# g29_load_cell.net
KiCad netlist of a schematic drawn in EAGLE
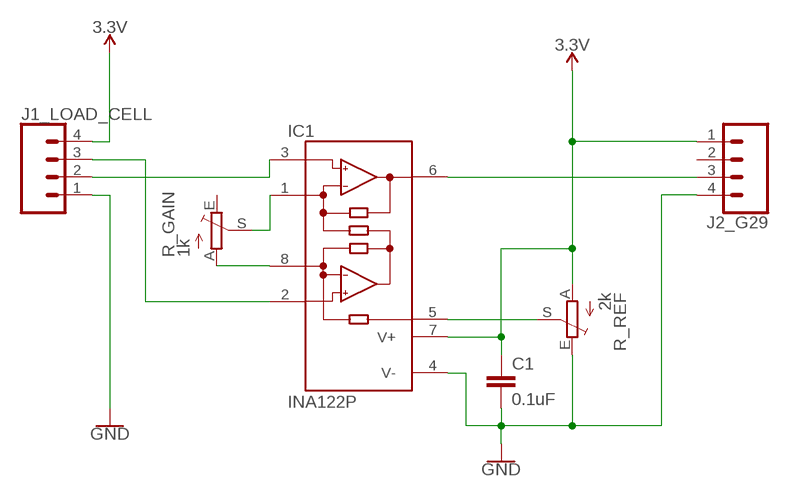
[diagram p0: schematic, sheet 1]

(export (version "E")
  (design (tool "Eeschema 10.0.6"))
  (components
    (comp (ref "C1")
      (value "0.1uF")
      (footprint "eagle-import:C025-024X044")
      (libsource (lib "eagle-import") (part "C-EU025-024X044"))
    )
    (comp (ref "IC1")
      (value "INA122P")
      (footprint "eagle-import:DIL08")
      (fields (field (name "MF") "TEXAS INSTRUMENTS"))
      (libsource (lib "eagle-import") (part "INA122P"))
    )
    (comp (ref "J1_LOAD_CELL")
      (value "CONN_04SCREW")
      (footprint "eagle-import:SCREWTERMINAL-3.5MM-4")
      (libsource (lib "eagle-import") (part "CONN_04SCREW"))
    )
    (comp (ref "J2_G29")
      (value "CONN_04SCREW")
      (footprint "eagle-import:SCREWTERMINAL-3.5MM-4")
      (libsource (lib "eagle-import") (part "CONN_04SCREW"))
    )
    (comp (ref "R_GAIN")
      (value "1k")
      (footprint "eagle-import:RJ9W")
      (libsource (lib "eagle-import") (part "TRIM_EU-RJ9W"))
    )
    (comp (ref "R_REF")
      (value "2k")
      (footprint "eagle-import:RJ9W")
      (libsource (lib "eagle-import") (part "TRIM_EU-RJ9W"))
    )
  )
  (nets
    (net (code "1") (name "3.3V") (class "Default")
      (node (ref "C1") (pin "1") (pinfunction "1_1") (pintype "passive"))
      (node (ref "IC1") (pin "7") (pinfunction "V+_7") (pintype "power_in"))
      (node (ref "J1_LOAD_CELL") (pin "4") (pinfunction "4_4") (pintype "passive"))
      (node (ref "J2_G29") (pin "1") (pinfunction "1_1") (pintype "passive"))
      (node (ref "R_REF") (pin "A") (pinfunction "A_A") (pintype "passive"))
    )
    (net (code "2") (name "GND") (class "Default")
      (node (ref "C1") (pin "2") (pinfunction "2_2") (pintype "passive"))
      (node (ref "IC1") (pin "4") (pinfunction "V-_4") (pintype "power_in"))
      (node (ref "J1_LOAD_CELL") (pin "1") (pinfunction "1_1") (pintype "passive"))
      (node (ref "J2_G29") (pin "4") (pinfunction "4_4") (pintype "passive"))
      (node (ref "R_REF") (pin "E") (pinfunction "E_E") (pintype "passive"))
    )
    (net (code "3") (name "Net-(IC1-+IN)") (class "Default")
      (node (ref "IC1") (pin "3") (pinfunction "+IN_3") (pintype "input"))
      (node (ref "J1_LOAD_CELL") (pin "2") (pinfunction "2_2") (pintype "passive"))
    )
    (net (code "4") (name "Net-(IC1--IN)") (class "Default")
      (node (ref "IC1") (pin "2") (pinfunction "-IN_2") (pintype "input"))
      (node (ref "J1_LOAD_CELL") (pin "3") (pinfunction "3_3") (pintype "passive"))
    )
    (net (code "5") (name "Net-(IC1-OUT)") (class "Default")
      (node (ref "IC1") (pin "6") (pinfunction "OUT_6") (pintype "output"))
      (node (ref "J2_G29") (pin "3") (pinfunction "3_3") (pintype "passive"))
    )
    (net (code "6") (name "Net-(IC1-REF)") (class "Default")
      (node (ref "IC1") (pin "5") (pinfunction "REF_5") (pintype "passive"))
      (node (ref "R_REF") (pin "S") (pinfunction "S_S") (pintype "passive"))
    )
    (net (code "7") (name "Net-(IC1-RG-Pad1)") (class "Default")
      (node (ref "IC1") (pin "1") (pinfunction "RG_1") (pintype "passive"))
      (node (ref "R_GAIN") (pin "S") (pinfunction "S_S") (pintype "passive"))
    )
    (net (code "8") (name "Net-(IC1-RG-Pad8)") (class "Default")
      (node (ref "IC1") (pin "8") (pinfunction "RG_8") (pintype "passive"))
      (node (ref "R_GAIN") (pin "A") (pinfunction "A_A") (pintype "passive"))
    )
    (net (code "9") (name "unconnected-(J2_G29-Pad2)") (class "Default")
      (node (ref "J2_G29") (pin "2") (pinfunction "2_2") (pintype "passive"))
    )
    (net (code "10") (name "unconnected-(R_GAIN-PadE)") (class "Default")
      (node (ref "R_GAIN") (pin "E") (pinfunction "E_E") (pintype "passive"))
    )
  )
)
